# 5V-12Visolated.net
KiCad netlist of a schematic drawn in Altium Designer
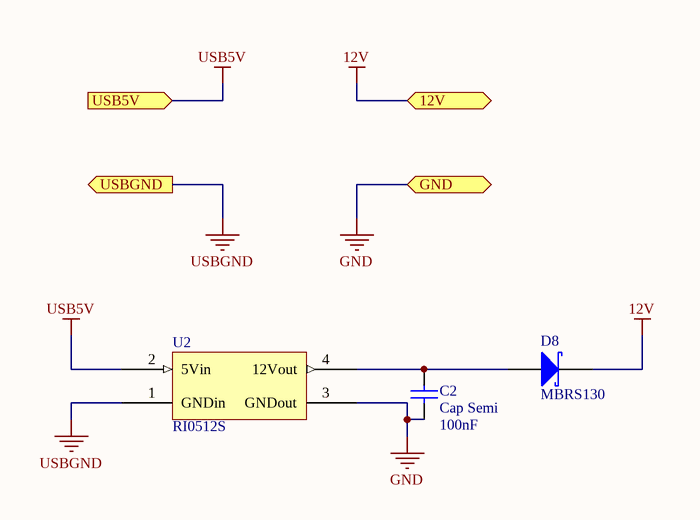
[diagram p0: 5V-12Visolated.SchDoc]

(export (version "E")
  (design (tool "Eeschema 10.0.6"))
  (components
    (comp (ref "C2")
      (value "Cap Semi")
      (footprint "0603")
      (description "Capacitor (Semiconductor SIM Model)")
      (fields (field (name "ALTIUM_VALUE") "100nF") (field (name "PUBLISHER") "Altium Limited"))
      (libsource (lib "Miscellaneous Devices") (part "Cap Semi"))
    )
    (comp (ref "D8")
      (value "MBRS130")
      (footprint "SMB")
      (description "Schottky Diode")
      (libsource (lib "RCLDQ") (part "D SCHOTTKY"))
    )
    (comp (ref "U2")
      (value "RI0512S")
      (footprint "RI0512S")
      (description "5V-12V isolated")
      (libsource (lib "DCDC-Converters") (part "RI0512S"))
    )
  )
  (nets
    (net (code "1") (name "12V") (class "Default")
      (node (ref "D8") (pin "K") (pinfunction "K_K") (pintype "passive"))
    )
    (net (code "2") (name "GND") (class "Default")
      (node (ref "C2") (pin "2") (pinfunction "2_2") (pintype "passive"))
      (node (ref "U2") (pin "3") (pinfunction "GNDout_3") (pintype "passive"))
    )
    (net (code "3") (name "Net-(U2-12Vout)") (class "Default")
      (node (ref "C2") (pin "1") (pinfunction "1_1") (pintype "passive"))
      (node (ref "D8") (pin "A") (pinfunction "A_A") (pintype "passive"))
      (node (ref "U2") (pin "4") (pinfunction "12Vout_4") (pintype "output"))
    )
    (net (code "4") (name "USB5V") (class "Default")
      (node (ref "U2") (pin "2") (pinfunction "5Vin_2") (pintype "input"))
    )
    (net (code "5") (name "USBGND") (class "Default")
      (node (ref "U2") (pin "1") (pinfunction "GNDin_1") (pintype "passive"))
    )
  )
)
